# Adafruit_LTC4311_I2C_Extender.net
KiCad netlist of a schematic drawn in EAGLE
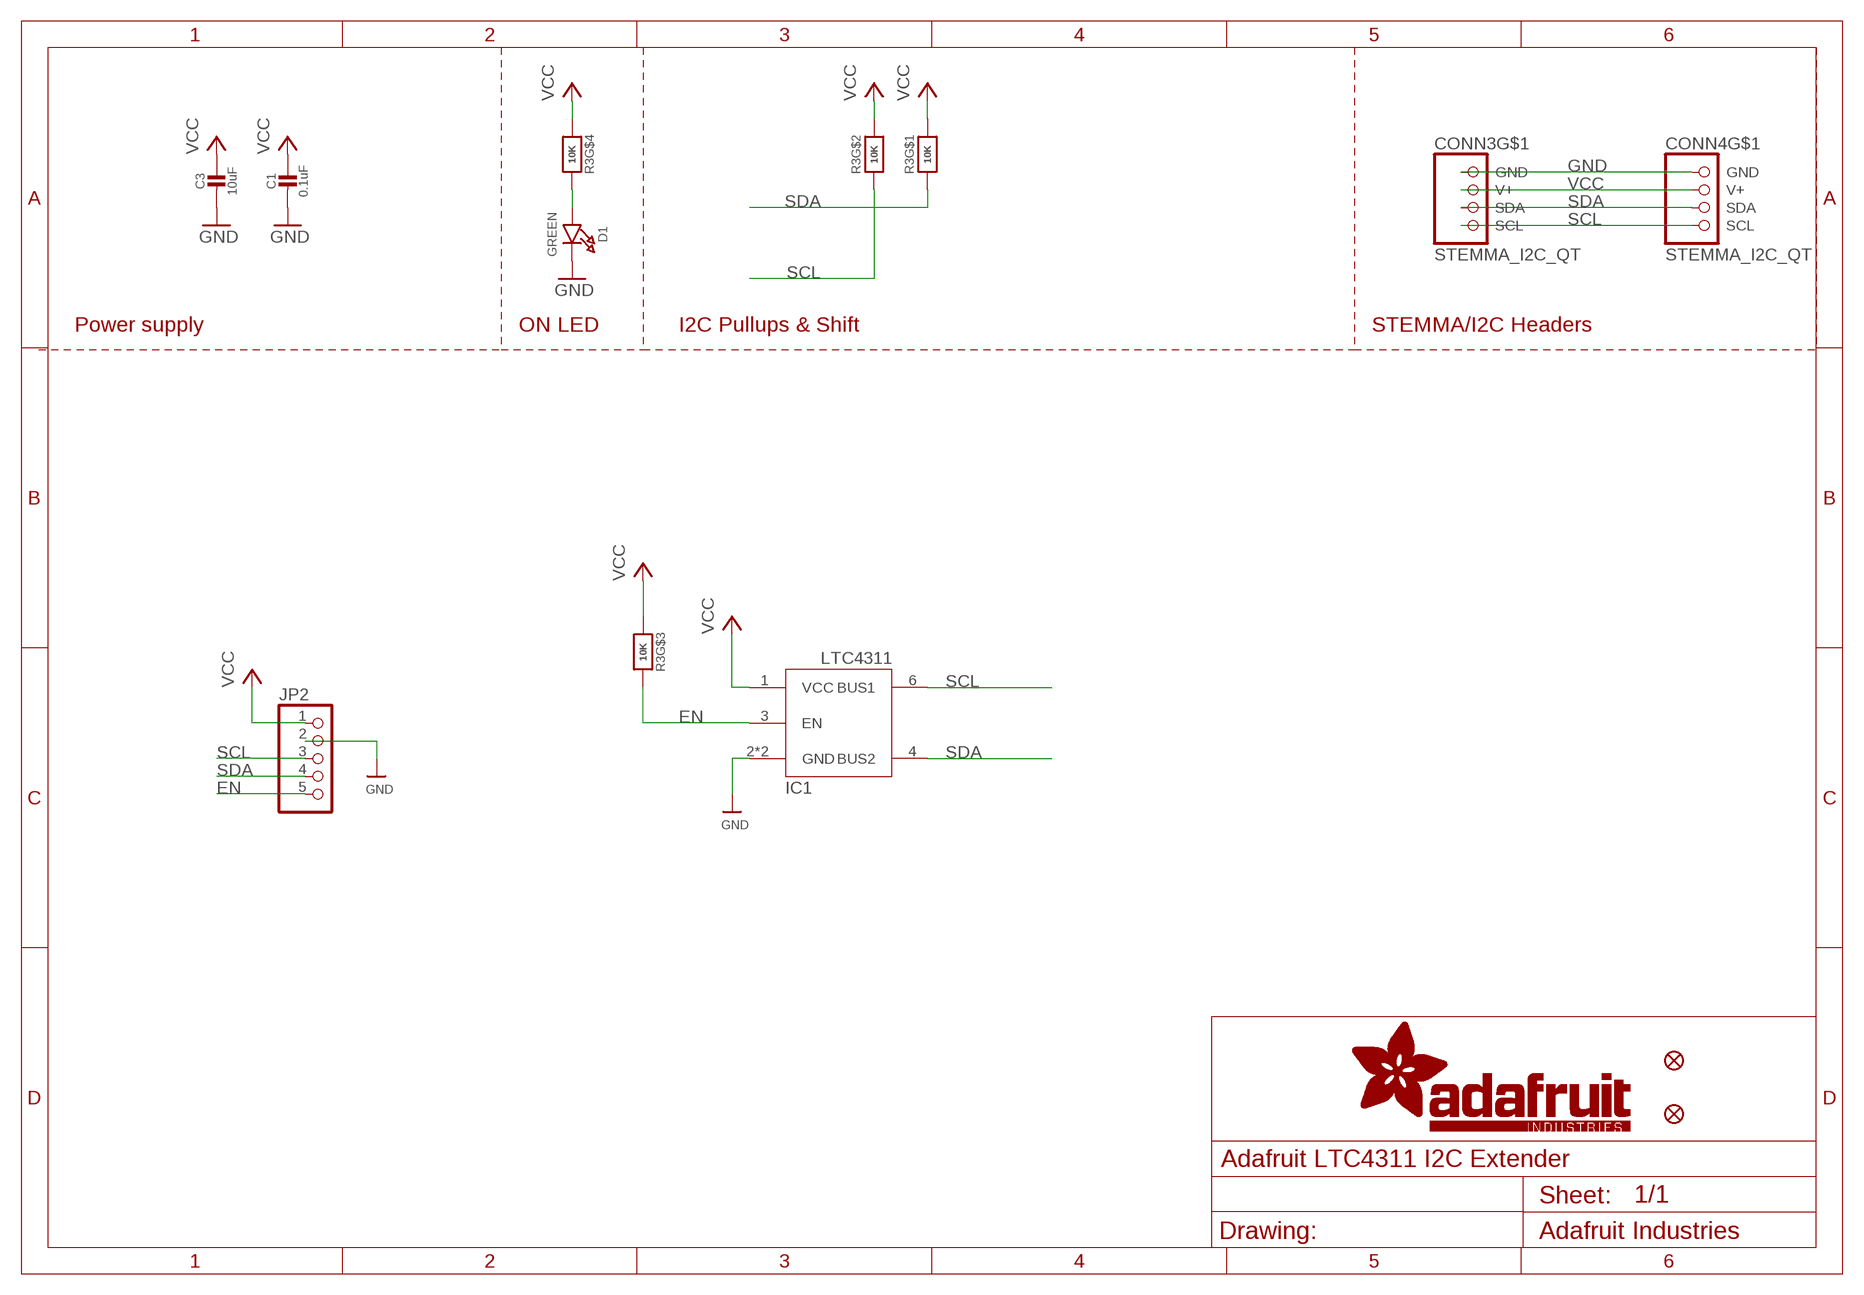
[diagram p0: schematic, sheet 1]

(export (version "E")
  (design (tool "Eeschema 10.0.6"))
  (components
    (comp (ref "C1")
      (value "0.1uF")
      (footprint "eagle-import:0603-NO")
      (libsource (lib "eagle-import") (part "CAP_CERAMIC0603_NO"))
    )
    (comp (ref "C3")
      (value "10uF")
      (footprint "eagle-import:0805-NO")
      (libsource (lib "eagle-import") (part "CAP_CERAMIC0805-NOOUTLINE"))
    )
    (comp (ref "CONN3")
      (value "STEMMA_I2C_QT")
      (footprint "eagle-import:JST_SH4")
      (libsource (lib "eagle-import") (part "STEMMA_I2C_QT"))
    )
    (comp (ref "CONN4")
      (value "STEMMA_I2C_QT")
      (footprint "eagle-import:JST_SH4")
      (libsource (lib "eagle-import") (part "STEMMA_I2C_QT"))
    )
    (comp (ref "D1")
      (value "GREEN")
      (footprint "eagle-import:CHIPLED_0603_NOOUTLINE")
      (libsource (lib "eagle-import") (part "LED0603_NOOUTLINE"))
    )
    (comp (ref "FID3")
      (value "FIDUCIAL_1MM")
      (footprint "eagle-import:FIDUCIAL_1MM")
      (libsource (lib "eagle-import") (part "FIDUCIAL_1MM"))
    )
    (comp (ref "FID4")
      (value "FIDUCIAL_1MM")
      (footprint "eagle-import:FIDUCIAL_1MM")
      (libsource (lib "eagle-import") (part "FIDUCIAL_1MM"))
    )
    (comp (ref "IC1")
      (value "LTC4311_SC70")
      (footprint "eagle-import:SC70-6L")
      (libsource (lib "eagle-import") (part "LTC4311_SC70"))
    )
    (comp (ref "JP2")
      (value "HEADER-1X570MIL")
      (footprint "eagle-import:1X05_ROUND_70")
      (libsource (lib "eagle-import") (part "HEADER-1X570MIL"))
    )
    (comp (ref "R3")
      (value "10K")
      (footprint "eagle-import:RESPACK_4X0603")
      (libsource (lib "eagle-import") (part "RESISTOR_4PACK"))
    )
  )
  (nets
    (net (code "1") (name "/EN") (class "Default")
      (node (ref "IC1") (pin "3") (pinfunction "EN_3") (pintype "input"))
      (node (ref "JP2") (pin "5") (pinfunction "5_5") (pintype "passive"))
      (node (ref "R3") (pin "6") (pinfunction "2_6") (pintype "passive"))
    )
    (net (code "2") (name "/SCL") (class "Default")
      (node (ref "CONN3") (pin "4") (pinfunction "SCL_4") (pintype "passive"))
      (node (ref "CONN4") (pin "4") (pinfunction "SCL_4") (pintype "passive"))
      (node (ref "IC1") (pin "6") (pinfunction "BUS1_6") (pintype "bidirectional"))
      (node (ref "JP2") (pin "3") (pinfunction "3_3") (pintype "passive"))
      (node (ref "R3") (pin "2") (pinfunction "1_2") (pintype "passive"))
    )
    (net (code "3") (name "/SDA") (class "Default")
      (node (ref "CONN3") (pin "3") (pinfunction "SDA_3") (pintype "passive"))
      (node (ref "CONN4") (pin "3") (pinfunction "SDA_3") (pintype "passive"))
      (node (ref "IC1") (pin "4") (pinfunction "BUS2_4") (pintype "bidirectional"))
      (node (ref "JP2") (pin "4") (pinfunction "4_4") (pintype "passive"))
      (node (ref "R3") (pin "1") (pinfunction "1_1") (pintype "passive"))
    )
    (net (code "4") (name "GND") (class "Default")
      (node (ref "C1") (pin "2") (pinfunction "2_2") (pintype "passive"))
      (node (ref "C3") (pin "2") (pinfunction "2_2") (pintype "passive"))
      (node (ref "CONN3") (pin "1") (pinfunction "GND_1") (pintype "passive"))
      (node (ref "CONN4") (pin "1") (pinfunction "GND_1") (pintype "passive"))
      (node (ref "D1") (pin "C") (pinfunction "C_C") (pintype "passive"))
      (node (ref "IC1") (pin "2") (pinfunction "GND_2") (pintype "power_in"))
      (node (ref "IC1") (pin "5") (pinfunction "GND_5") (pintype "power_in"))
      (node (ref "JP2") (pin "2") (pinfunction "2_2") (pintype "passive"))
    )
    (net (code "5") (name "Net-(R3D-2)") (class "Default")
      (node (ref "D1") (pin "A") (pinfunction "A_A") (pintype "passive"))
      (node (ref "R3") (pin "5") (pinfunction "2_5") (pintype "passive"))
    )
    (net (code "6") (name "VCC") (class "Default")
      (node (ref "C1") (pin "1") (pinfunction "1_1") (pintype "passive"))
      (node (ref "C3") (pin "1") (pinfunction "1_1") (pintype "passive"))
      (node (ref "CONN3") (pin "2") (pinfunction "V+_2") (pintype "passive"))
      (node (ref "CONN4") (pin "2") (pinfunction "V+_2") (pintype "passive"))
      (node (ref "IC1") (pin "1") (pinfunction "VCC_1") (pintype "power_in"))
      (node (ref "JP2") (pin "1") (pinfunction "1_1") (pintype "passive"))
      (node (ref "R3") (pin "3") (pinfunction "1_3") (pintype "passive"))
      (node (ref "R3") (pin "4") (pinfunction "1_4") (pintype "passive"))
      (node (ref "R3") (pin "7") (pinfunction "2_7") (pintype "passive"))
      (node (ref "R3") (pin "8") (pinfunction "2_8") (pintype "passive"))
    )
  )
)
